# c64saver_1_1.net
KiCad netlist of a schematic drawn in EAGLE
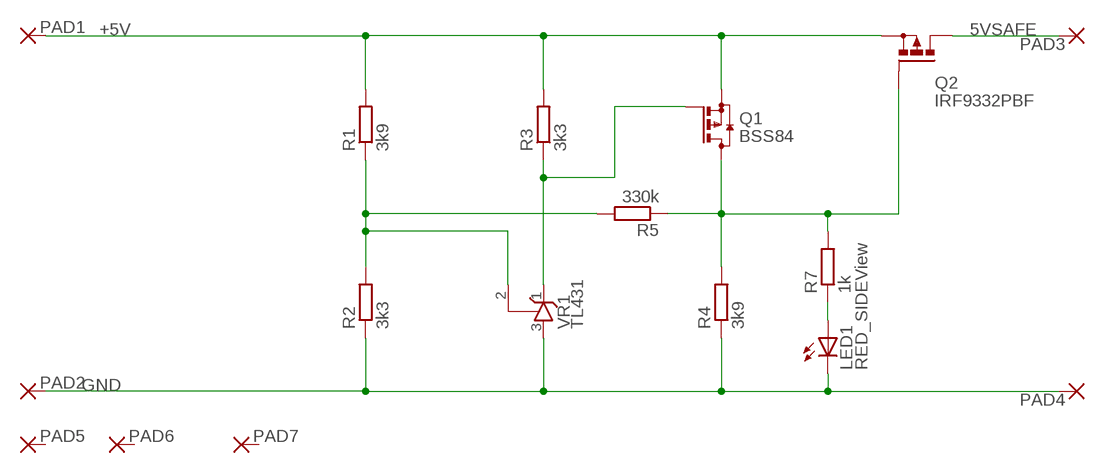
[diagram p0: schematic, sheet 1]

(export (version "E")
  (design (tool "Eeschema 10.0.6"))
  (components
    (comp (ref "LED1")
      (value "RED_SIDEView")
      (footprint "eagle-import:CHIPLED_1206")
      (libsource (lib "eagle-import") (part "LEDCHIPLED_1206"))
    )
    (comp (ref "PAD1")
      (value "WIREPADSMD1,27-254")
      (footprint "eagle-import:SMD1,27-2,54")
      (libsource (lib "eagle-import") (part "WIREPADSMD1,27-254"))
    )
    (comp (ref "PAD2")
      (value "WIREPADSMD1,27-254")
      (footprint "eagle-import:SMD1,27-2,54")
      (libsource (lib "eagle-import") (part "WIREPADSMD1,27-254"))
    )
    (comp (ref "PAD3")
      (value "WIREPADSMD1,27-254")
      (footprint "eagle-import:SMD1,27-2,54")
      (libsource (lib "eagle-import") (part "WIREPADSMD1,27-254"))
    )
    (comp (ref "PAD4")
      (value "WIREPADSMD1,27-254")
      (footprint "eagle-import:SMD1,27-2,54")
      (libsource (lib "eagle-import") (part "WIREPADSMD1,27-254"))
    )
    (comp (ref "PAD5")
      (value "WIREPADSMD1,27-254")
      (footprint "eagle-import:SMD1,27-2,54")
      (libsource (lib "eagle-import") (part "WIREPADSMD1,27-254"))
    )
    (comp (ref "PAD6")
      (value "WIREPADSMD1,27-254")
      (footprint "eagle-import:SMD1,27-2,54")
      (libsource (lib "eagle-import") (part "WIREPADSMD1,27-254"))
    )
    (comp (ref "PAD7")
      (value "WIREPADSMD1,27-254")
      (footprint "eagle-import:SMD1,27-2,54")
      (libsource (lib "eagle-import") (part "WIREPADSMD1,27-254"))
    )
    (comp (ref "Q1")
      (value "BSS84")
      (footprint "eagle-import:SOT23")
      (libsource (lib "eagle-import") (part "BSS84"))
    )
    (comp (ref "Q2")
      (value "IRF9332PBF")
      (footprint "eagle-import:SO-08")
      (libsource (lib "eagle-import") (part "P-MOSFET-SO8"))
    )
    (comp (ref "R1")
      (value "3k9")
      (footprint "eagle-import:R0603")
      (libsource (lib "eagle-import") (part "R-EU_R0603"))
    )
    (comp (ref "R2")
      (value "3k3")
      (footprint "eagle-import:R0603")
      (libsource (lib "eagle-import") (part "R-EU_R0603"))
    )
    (comp (ref "R3")
      (value "3k3")
      (footprint "eagle-import:R0603")
      (libsource (lib "eagle-import") (part "R-EU_R0603"))
    )
    (comp (ref "R4")
      (value "3k9")
      (footprint "eagle-import:R0603")
      (libsource (lib "eagle-import") (part "R-EU_R0603"))
    )
    (comp (ref "R5")
      (value "330k")
      (footprint "eagle-import:R0603")
      (libsource (lib "eagle-import") (part "R-EU_R0603"))
    )
    (comp (ref "R7")
      (value "1k")
      (footprint "eagle-import:R0603")
      (libsource (lib "eagle-import") (part "R-EU_R0603"))
    )
    (comp (ref "VR1")
      (value "TL431")
      (footprint "eagle-import:SOT23")
      (libsource (lib "eagle-import") (part "TL431CLPSOT23"))
    )
  )
  (nets
    (net (code "1") (name "/+5V") (class "Default")
      (node (ref "PAD1") (pin "1") (pinfunction "P_1") (pintype "passive"))
      (node (ref "Q1") (pin "2") (pinfunction "S_2") (pintype "passive"))
      (node (ref "Q2") (pin "1") (pinfunction "S_1") (pintype "passive"))
      (node (ref "Q2") (pin "2") (pinfunction "S_2") (pintype "passive"))
      (node (ref "Q2") (pin "3") (pinfunction "S_3") (pintype "passive"))
      (node (ref "R1") (pin "2") (pinfunction "2_2") (pintype "passive"))
      (node (ref "R3") (pin "2") (pinfunction "2_2") (pintype "passive"))
    )
    (net (code "2") (name "/5VSAFE") (class "Default")
      (node (ref "PAD3") (pin "1") (pinfunction "P_1") (pintype "passive"))
      (node (ref "Q2") (pin "5") (pinfunction "D_5") (pintype "passive"))
      (node (ref "Q2") (pin "6") (pinfunction "D_6") (pintype "passive"))
      (node (ref "Q2") (pin "7") (pinfunction "D_7") (pintype "passive"))
      (node (ref "Q2") (pin "8") (pinfunction "D_8") (pintype "passive"))
    )
    (net (code "3") (name "/GND") (class "Default")
      (node (ref "LED1") (pin "C") (pinfunction "C_C") (pintype "passive"))
      (node (ref "PAD2") (pin "1") (pinfunction "P_1") (pintype "passive"))
      (node (ref "PAD4") (pin "1") (pinfunction "P_1") (pintype "passive"))
      (node (ref "R2") (pin "1") (pinfunction "1_1") (pintype "passive"))
      (node (ref "R4") (pin "1") (pinfunction "1_1") (pintype "passive"))
      (node (ref "VR1") (pin "3") (pinfunction "A_3") (pintype "passive"))
    )
    (net (code "4") (name "Net-(LED1-PadA)") (class "Default")
      (node (ref "LED1") (pin "A") (pinfunction "A_A") (pintype "passive"))
      (node (ref "R7") (pin "1") (pinfunction "1_1") (pintype "passive"))
    )
    (net (code "5") (name "Net-(Q1-D)") (class "Default")
      (node (ref "Q1") (pin "3") (pinfunction "D_3") (pintype "passive"))
      (node (ref "Q2") (pin "4") (pinfunction "G_4") (pintype "passive"))
      (node (ref "R4") (pin "2") (pinfunction "2_2") (pintype "passive"))
      (node (ref "R5") (pin "1") (pinfunction "1_1") (pintype "passive"))
      (node (ref "R7") (pin "2") (pinfunction "2_2") (pintype "passive"))
    )
    (net (code "6") (name "Net-(Q1-G)") (class "Default")
      (node (ref "Q1") (pin "1") (pinfunction "G_1") (pintype "passive"))
      (node (ref "R3") (pin "1") (pinfunction "1_1") (pintype "passive"))
      (node (ref "VR1") (pin "1") (pinfunction "C_1") (pintype "passive"))
    )
    (net (code "7") (name "Net-(VR1-R)") (class "Default")
      (node (ref "R1") (pin "1") (pinfunction "1_1") (pintype "passive"))
      (node (ref "R2") (pin "2") (pinfunction "2_2") (pintype "passive"))
      (node (ref "R5") (pin "2") (pinfunction "2_2") (pintype "passive"))
      (node (ref "VR1") (pin "2") (pinfunction "R_2") (pintype "passive"))
    )
    (net (code "8") (name "unconnected-(PAD5-P-Pad1)") (class "Default")
      (node (ref "PAD5") (pin "1") (pinfunction "P_1") (pintype "passive"))
    )
    (net (code "9") (name "unconnected-(PAD6-P-Pad1)") (class "Default")
      (node (ref "PAD6") (pin "1") (pinfunction "P_1") (pintype "passive"))
    )
    (net (code "10") (name "unconnected-(PAD7-P-Pad1)") (class "Default")
      (node (ref "PAD7") (pin "1") (pinfunction "P_1") (pintype "passive"))
    )
  )
)
